# Solar_Tracker.net
KiCad netlist of a schematic drawn in Altium Designer
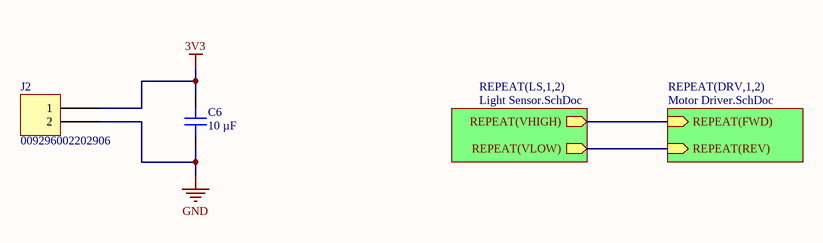
[diagram p0: Solar Tracker.SchDoc]

(export (version "E")
  (design (tool "Eeschema 10.0.6"))
  (components
    (comp (ref "C6")
      (value "10 µF")
      (footprint "CAP 1210_3225 - 1MM")
      (description "CAP CER 10UF 16V X5R 1210")
      (fields
        (field (name "PART NUMBER") "CL32A106MOJNNNE")
        (field (name "MANUFACTURER") "Samsung Electro-Mechanics")
      )
      (libsource (lib "altiumlibrary.com") (part "Capacitor"))
    )
    (comp (ref "J2")
      (value "009296002202906")
      (footprint "AVX 9296002202806")
      (description "CONN WIRE POKE-IN 2POS SMD RA")
      (fields (field (name "MANUFACTURER") "AVX Corporation"))
      (libsource (lib "altiumlibrary.com") (part "2 Pin"))
    )
  )
  (nets
    (net (code "3") (name "3V3") (class "Default")
      (node (ref "C6") (pin "2") (pinfunction "2_2") (pintype "passive"))
      (node (ref "J2") (pin "1") (pinfunction "1_1") (pintype "passive"))
    )
    (net (code "4") (name "GND") (class "Default")
      (node (ref "C6") (pin "1") (pinfunction "1_1") (pintype "passive"))
      (node (ref "J2") (pin "2") (pinfunction "2_2") (pintype "passive"))
    )
  )
)
